# Atmega32u2_breakout.net
KiCad netlist of a schematic drawn in EAGLE
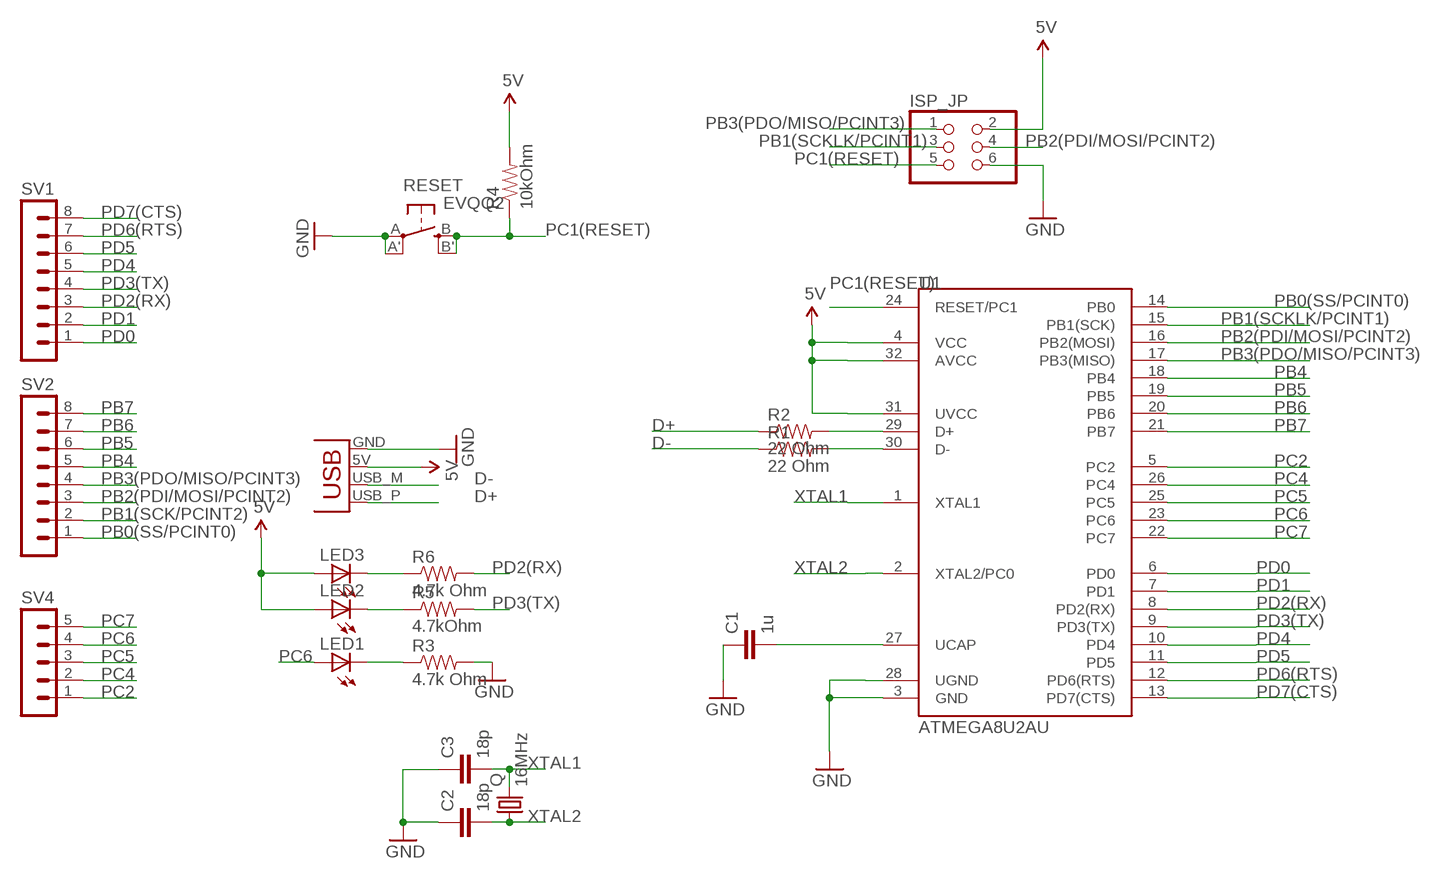
[diagram p0: schematic, sheet 1]

(export (version "E")
  (design (tool "Eeschema 10.0.6"))
  (components
    (comp (ref "C1")
      (value "1u")
      (footprint "eagle-import:0805")
      (libsource (lib "eagle-import") (part "CAP0805"))
    )
    (comp (ref "C2")
      (value "18p")
      (footprint "eagle-import:0805")
      (libsource (lib "eagle-import") (part "CAP0805"))
    )
    (comp (ref "C3")
      (value "18p")
      (footprint "eagle-import:0805")
      (libsource (lib "eagle-import") (part "CAP0805"))
    )
    (comp (ref "ISP_JP")
      (value "PINHD-2X3")
      (footprint "eagle-import:2X03")
      (libsource (lib "eagle-import") (part "PINHD-2X3"))
    )
    (comp (ref "LED1")
      (value "LED0603")
      (footprint "eagle-import:LED-0603")
      (libsource (lib "eagle-import") (part "LED0603"))
    )
    (comp (ref "LED2")
      (value "LED0603")
      (footprint "eagle-import:LED-0603")
      (libsource (lib "eagle-import") (part "LED0603"))
    )
    (comp (ref "LED3")
      (value "LED0603")
      (footprint "eagle-import:LED-0603")
      (libsource (lib "eagle-import") (part "LED0603"))
    )
    (comp (ref "Q")
      (value "16MHz")
      (footprint "eagle-import:HC49US")
      (libsource (lib "eagle-import") (part "CRYSTALHC49US"))
    )
    (comp (ref "R1")
      (value "22 Ohm")
      (footprint "eagle-import:0805")
      (libsource (lib "eagle-import") (part "RESISTOR"))
    )
    (comp (ref "R2")
      (value "22 Ohm")
      (footprint "eagle-import:0805")
      (libsource (lib "eagle-import") (part "RESISTOR"))
    )
    (comp (ref "R3")
      (value "4.7k Ohm")
      (footprint "eagle-import:0805")
      (libsource (lib "eagle-import") (part "RESISTOR"))
    )
    (comp (ref "R4")
      (value "10kOhm")
      (footprint "eagle-import:0805")
      (libsource (lib "eagle-import") (part "RESISTOR"))
    )
    (comp (ref "R5")
      (value "4.7kOhm")
      (footprint "eagle-import:0805")
      (libsource (lib "eagle-import") (part "RESISTOR"))
    )
    (comp (ref "R6")
      (value "4.7k Ohm")
      (footprint "eagle-import:0805")
      (libsource (lib "eagle-import") (part "RESISTOR"))
    )
    (comp (ref "RESET")
      (value "EVQQ2")
      (footprint "eagle-import:EVQ-Q2")
      (libsource (lib "eagle-import") (part "EVQQ2"))
    )
    (comp (ref "SV1")
      (value "MA08-1")
      (footprint "eagle-import:MA08-1")
      (libsource (lib "eagle-import") (part "MA08-1"))
    )
    (comp (ref "SV2")
      (value "MA08-1")
      (footprint "eagle-import:MA08-1")
      (libsource (lib "eagle-import") (part "MA08-1"))
    )
    (comp (ref "SV4")
      (value "MA05-1")
      (footprint "eagle-import:MA05-1")
      (libsource (lib "eagle-import") (part "MA05-1"))
    )
    (comp (ref "U1")
      (value "ATMEGA8U2AU")
      (footprint "eagle-import:TQFP32-08")
      (libsource (lib "eagle-import") (part "ATMEGA8U2AU"))
    )
    (comp (ref "X1")
      (value "USBPCB")
      (footprint "eagle-import:USB-A-PCB")
      (libsource (lib "eagle-import") (part "USBPCB"))
    )
  )
  (nets
    (net (code "1") (name "/D+") (class "Default")
      (node (ref "R2") (pin "1") (pinfunction "1_1") (pintype "passive"))
      (node (ref "X1") (pin "USB_P") (pinfunction "D+_USB_P") (pintype "bidirectional"))
    )
    (net (code "2") (name "/D-") (class "Default")
      (node (ref "R1") (pin "1") (pinfunction "1_1") (pintype "passive"))
      (node (ref "X1") (pin "USB_M") (pinfunction "D-_USB_M") (pintype "bidirectional"))
    )
    (net (code "3") (name "/PB0(SS{slash}PCINT0)") (class "Default")
      (node (ref "SV2") (pin "1") (pinfunction "1_1") (pintype "passive"))
      (node (ref "U1") (pin "14") (pinfunction "PB0_14") (pintype "bidirectional"))
    )
    (net (code "4") (name "/PB1(SCKLK{slash}PCINT1)") (class "Default")
      (node (ref "ISP_JP") (pin "3") (pinfunction "3_3") (pintype "passive"))
      (node (ref "U1") (pin "15") (pinfunction "PB1(SCK)_15") (pintype "bidirectional"))
    )
    (net (code "5") (name "/PB1(SCK{slash}PCINT2)") (class "Default")
      (node (ref "SV2") (pin "2") (pinfunction "2_2") (pintype "passive"))
    )
    (net (code "6") (name "/PB2(PDI{slash}MOSI{slash}PCINT2)") (class "Default")
      (node (ref "ISP_JP") (pin "4") (pinfunction "4_4") (pintype "passive"))
      (node (ref "SV2") (pin "3") (pinfunction "3_3") (pintype "passive"))
      (node (ref "U1") (pin "16") (pinfunction "PB2(MOSI)_16") (pintype "bidirectional"))
    )
    (net (code "7") (name "/PB3(PDO{slash}MISO{slash}PCINT3)") (class "Default")
      (node (ref "ISP_JP") (pin "1") (pinfunction "1_1") (pintype "passive"))
      (node (ref "SV2") (pin "4") (pinfunction "4_4") (pintype "passive"))
      (node (ref "U1") (pin "17") (pinfunction "PB3(MISO)_17") (pintype "bidirectional"))
    )
    (net (code "8") (name "/PB4") (class "Default")
      (node (ref "SV2") (pin "5") (pinfunction "5_5") (pintype "passive"))
      (node (ref "U1") (pin "18") (pinfunction "PB4_18") (pintype "bidirectional"))
    )
    (net (code "9") (name "/PB5") (class "Default")
      (node (ref "SV2") (pin "6") (pinfunction "6_6") (pintype "passive"))
      (node (ref "U1") (pin "19") (pinfunction "PB5_19") (pintype "bidirectional"))
    )
    (net (code "10") (name "/PB6") (class "Default")
      (node (ref "SV2") (pin "7") (pinfunction "7_7") (pintype "passive"))
      (node (ref "U1") (pin "20") (pinfunction "PB6_20") (pintype "bidirectional"))
    )
    (net (code "11") (name "/PB7") (class "Default")
      (node (ref "SV2") (pin "8") (pinfunction "8_8") (pintype "passive"))
      (node (ref "U1") (pin "21") (pinfunction "PB7_21") (pintype "bidirectional"))
    )
    (net (code "12") (name "/PC1(RESET)") (class "Default")
      (node (ref "ISP_JP") (pin "5") (pinfunction "5_5") (pintype "passive"))
      (node (ref "R4") (pin "1") (pinfunction "1_1") (pintype "passive"))
      (node (ref "RESET") (pin "B") (pinfunction "S_B") (pintype "passive"))
      (node (ref "RESET") (pin "B'") (pinfunction "S1_B'") (pintype "passive"))
      (node (ref "U1") (pin "24") (pinfunction "RESET/PC1_24") (pintype "bidirectional"))
    )
    (net (code "13") (name "/PC2") (class "Default")
      (node (ref "SV4") (pin "1") (pinfunction "1_1") (pintype "passive"))
      (node (ref "U1") (pin "5") (pinfunction "PC2_5") (pintype "bidirectional"))
    )
    (net (code "14") (name "/PC4") (class "Default")
      (node (ref "SV4") (pin "2") (pinfunction "2_2") (pintype "passive"))
      (node (ref "U1") (pin "26") (pinfunction "PC4_26") (pintype "bidirectional"))
    )
    (net (code "15") (name "/PC5") (class "Default")
      (node (ref "SV4") (pin "3") (pinfunction "3_3") (pintype "passive"))
      (node (ref "U1") (pin "25") (pinfunction "PC5_25") (pintype "bidirectional"))
    )
    (net (code "16") (name "/PC6") (class "Default")
      (node (ref "LED1") (pin "A") (pinfunction "A_A") (pintype "passive"))
      (node (ref "SV4") (pin "4") (pinfunction "4_4") (pintype "passive"))
      (node (ref "U1") (pin "23") (pinfunction "PC6_23") (pintype "bidirectional"))
    )
    (net (code "17") (name "/PC7") (class "Default")
      (node (ref "SV4") (pin "5") (pinfunction "5_5") (pintype "passive"))
      (node (ref "U1") (pin "22") (pinfunction "PC7_22") (pintype "bidirectional"))
    )
    (net (code "18") (name "/PD0") (class "Default")
      (node (ref "SV1") (pin "1") (pinfunction "1_1") (pintype "passive"))
      (node (ref "U1") (pin "6") (pinfunction "PD0_6") (pintype "bidirectional"))
    )
    (net (code "19") (name "/PD1") (class "Default")
      (node (ref "SV1") (pin "2") (pinfunction "2_2") (pintype "passive"))
      (node (ref "U1") (pin "7") (pinfunction "PD1_7") (pintype "bidirectional"))
    )
    (net (code "20") (name "/PD2(RX)") (class "Default")
      (node (ref "R6") (pin "2") (pinfunction "2_2") (pintype "passive"))
      (node (ref "SV1") (pin "3") (pinfunction "3_3") (pintype "passive"))
      (node (ref "U1") (pin "8") (pinfunction "PD2(RX)_8") (pintype "bidirectional"))
    )
    (net (code "21") (name "/PD3(TX)") (class "Default")
      (node (ref "R5") (pin "2") (pinfunction "2_2") (pintype "passive"))
      (node (ref "SV1") (pin "4") (pinfunction "4_4") (pintype "passive"))
      (node (ref "U1") (pin "9") (pinfunction "PD3(TX)_9") (pintype "bidirectional"))
    )
    (net (code "22") (name "/PD4") (class "Default")
      (node (ref "SV1") (pin "5") (pinfunction "5_5") (pintype "passive"))
      (node (ref "U1") (pin "10") (pinfunction "PD4_10") (pintype "bidirectional"))
    )
    (net (code "23") (name "/PD5") (class "Default")
      (node (ref "SV1") (pin "6") (pinfunction "6_6") (pintype "passive"))
      (node (ref "U1") (pin "11") (pinfunction "PD5_11") (pintype "bidirectional"))
    )
    (net (code "24") (name "/PD6(RTS)") (class "Default")
      (node (ref "SV1") (pin "7") (pinfunction "7_7") (pintype "passive"))
      (node (ref "U1") (pin "12") (pinfunction "PD6(RTS)_12") (pintype "bidirectional"))
    )
    (net (code "25") (name "/PD7(CTS)") (class "Default")
      (node (ref "SV1") (pin "8") (pinfunction "8_8") (pintype "passive"))
      (node (ref "U1") (pin "13") (pinfunction "PD7(CTS)_13") (pintype "bidirectional"))
    )
    (net (code "26") (name "/XTAL1") (class "Default")
      (node (ref "C3") (pin "2") (pinfunction "2_2") (pintype "passive"))
      (node (ref "Q") (pin "2") (pinfunction "2_2") (pintype "passive"))
      (node (ref "U1") (pin "1") (pinfunction "XTAL1_1") (pintype "bidirectional"))
    )
    (net (code "27") (name "/XTAL2") (class "Default")
      (node (ref "C2") (pin "2") (pinfunction "2_2") (pintype "passive"))
      (node (ref "Q") (pin "1") (pinfunction "1_1") (pintype "passive"))
      (node (ref "U1") (pin "2") (pinfunction "XTAL2/PC0_2") (pintype "bidirectional"))
    )
    (net (code "28") (name "5V") (class "Default")
      (node (ref "ISP_JP") (pin "2") (pinfunction "2_2") (pintype "passive"))
      (node (ref "LED2") (pin "A") (pinfunction "A_A") (pintype "passive"))
      (node (ref "LED3") (pin "A") (pinfunction "A_A") (pintype "passive"))
      (node (ref "R4") (pin "2") (pinfunction "2_2") (pintype "passive"))
      (node (ref "U1") (pin "31") (pinfunction "UVCC_31") (pintype "bidirectional"))
      (node (ref "U1") (pin "32") (pinfunction "AVCC_32") (pintype "bidirectional"))
      (node (ref "U1") (pin "4") (pinfunction "VCC_4") (pintype "bidirectional"))
      (node (ref "X1") (pin "5V") (pinfunction "VBUS_5V") (pintype "bidirectional"))
    )
    (net (code "29") (name "GND") (class "Default")
      (node (ref "C1") (pin "1") (pinfunction "1_1") (pintype "passive"))
      (node (ref "C2") (pin "1") (pinfunction "1_1") (pintype "passive"))
      (node (ref "C3") (pin "1") (pinfunction "1_1") (pintype "passive"))
      (node (ref "ISP_JP") (pin "6") (pinfunction "6_6") (pintype "passive"))
      (node (ref "R3") (pin "2") (pinfunction "2_2") (pintype "passive"))
      (node (ref "RESET") (pin "A") (pinfunction "P_A") (pintype "passive"))
      (node (ref "RESET") (pin "A'") (pinfunction "P1_A'") (pintype "passive"))
      (node (ref "U1") (pin "28") (pinfunction "UGND_28") (pintype "bidirectional"))
      (node (ref "U1") (pin "3") (pinfunction "GND_3") (pintype "bidirectional"))
      (node (ref "X1") (pin "GND") (pinfunction "GND_GND") (pintype "bidirectional"))
    )
    (net (code "30") (name "Net-(LED1-PadC)") (class "Default")
      (node (ref "LED1") (pin "C") (pinfunction "C_C") (pintype "passive"))
      (node (ref "R3") (pin "1") (pinfunction "1_1") (pintype "passive"))
    )
    (net (code "31") (name "Net-(LED2-PadC)") (class "Default")
      (node (ref "LED2") (pin "C") (pinfunction "C_C") (pintype "passive"))
      (node (ref "R5") (pin "1") (pinfunction "1_1") (pintype "passive"))
    )
    (net (code "32") (name "Net-(LED3-PadC)") (class "Default")
      (node (ref "LED3") (pin "C") (pinfunction "C_C") (pintype "passive"))
      (node (ref "R6") (pin "1") (pinfunction "1_1") (pintype "passive"))
    )
    (net (code "33") (name "Net-(U1-D+)") (class "Default")
      (node (ref "R2") (pin "2") (pinfunction "2_2") (pintype "passive"))
      (node (ref "U1") (pin "29") (pinfunction "D+_29") (pintype "bidirectional"))
    )
    (net (code "34") (name "Net-(U1-D-)") (class "Default")
      (node (ref "R1") (pin "2") (pinfunction "2_2") (pintype "passive"))
      (node (ref "U1") (pin "30") (pinfunction "D-_30") (pintype "bidirectional"))
    )
    (net (code "35") (name "Net-(U1-UCAP)") (class "Default")
      (node (ref "C1") (pin "2") (pinfunction "2_2") (pintype "passive"))
      (node (ref "U1") (pin "27") (pinfunction "UCAP_27") (pintype "bidirectional"))
    )
  )
)
